# Sensor_Board.net
KiCad netlist of a schematic drawn in EAGLE
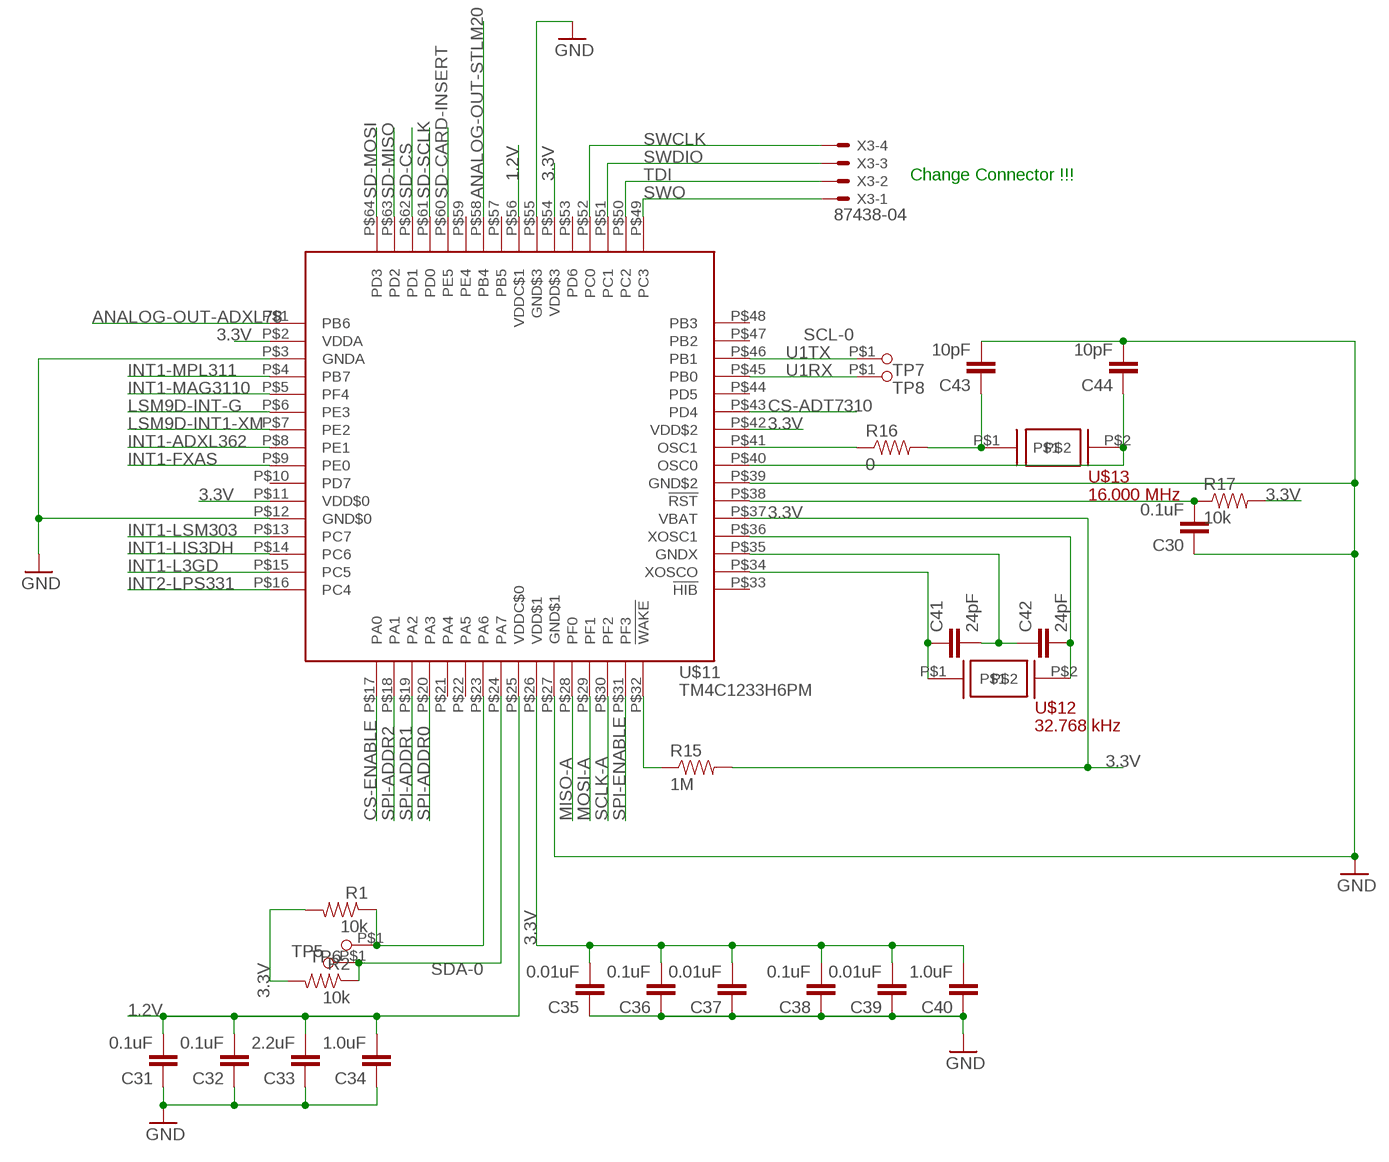
[diagram p0: schematic, sheet 1]
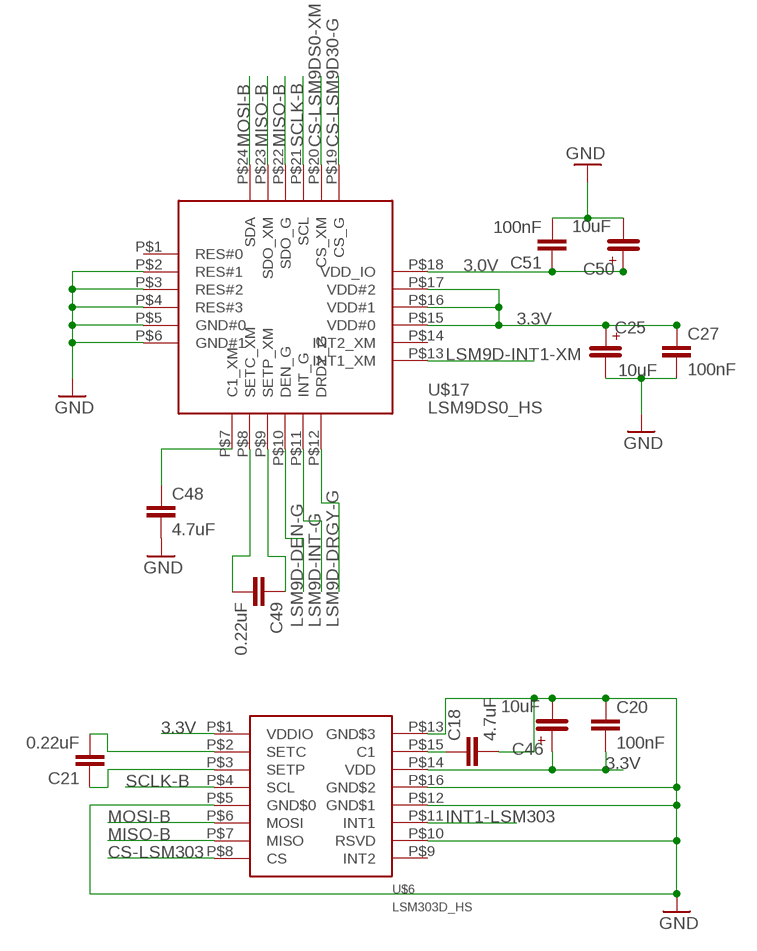
[diagram p1: schematic, sheet 2]
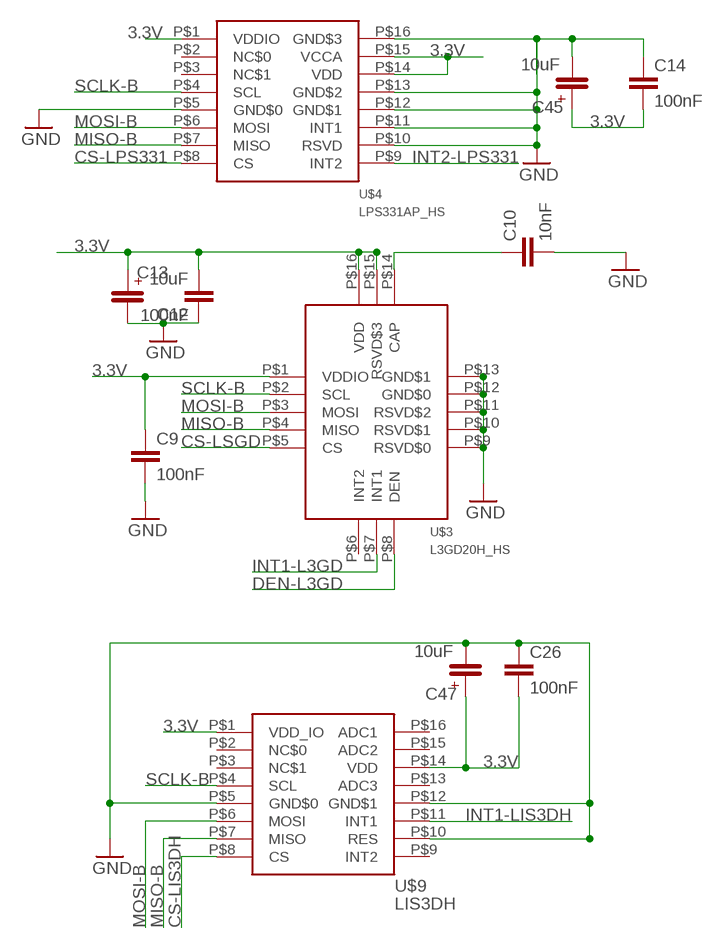
[diagram p2: schematic, sheet 3]
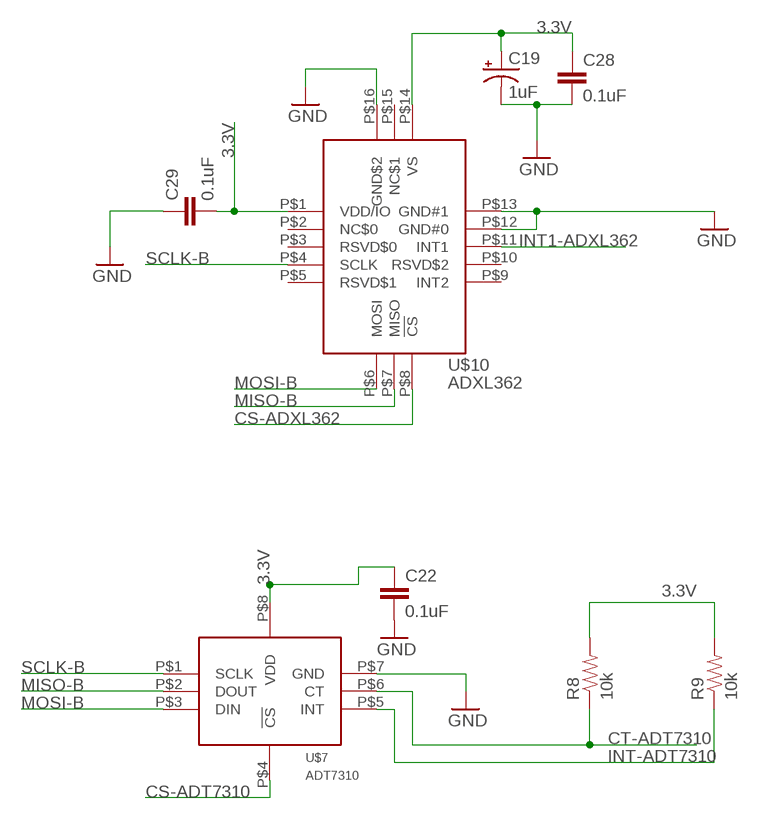
[diagram p3: schematic, sheet 4]
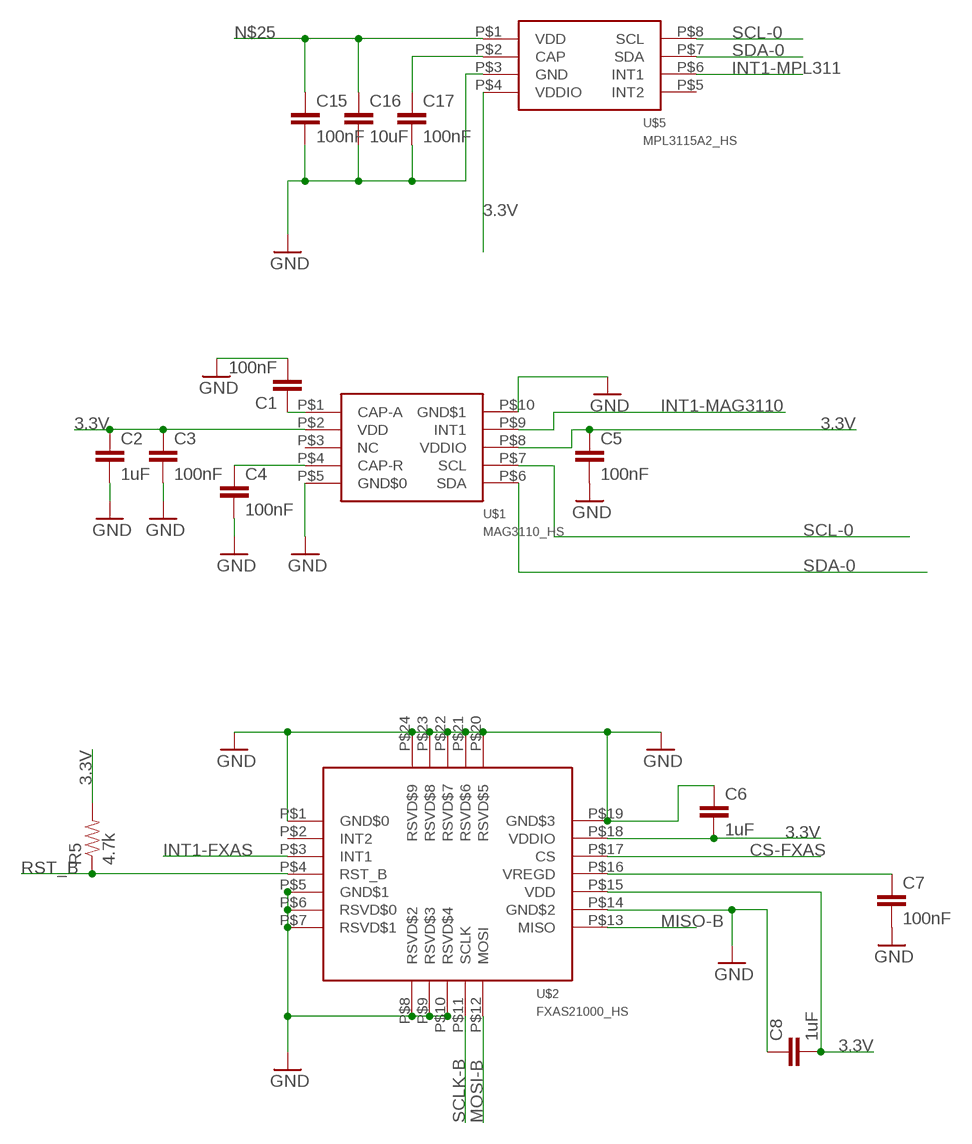
[diagram p4: schematic, sheet 5]
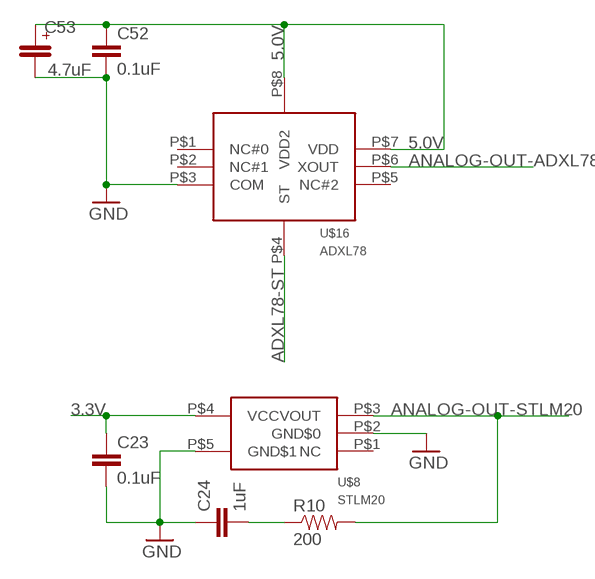
[diagram p5: schematic, sheet 6]
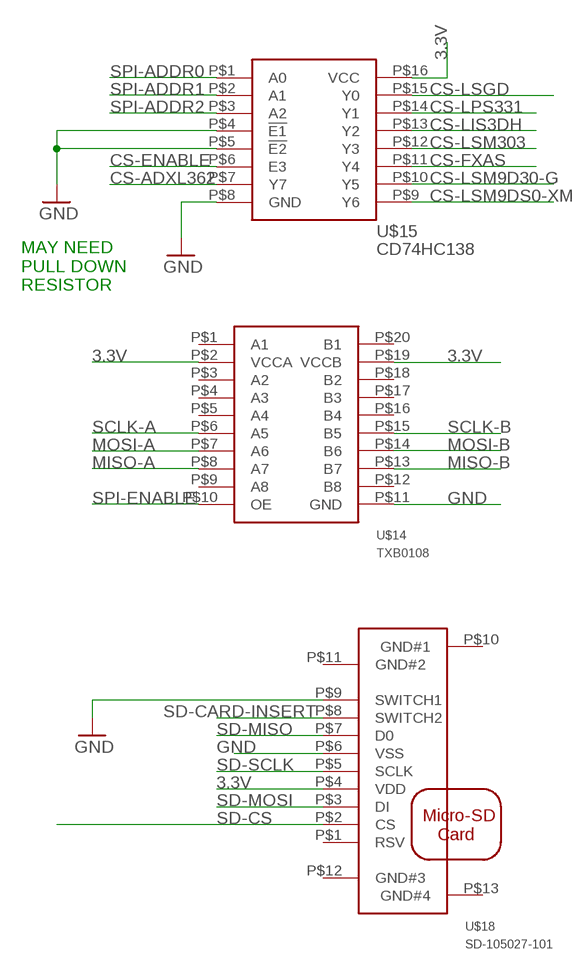
[diagram p6: schematic, sheet 7]
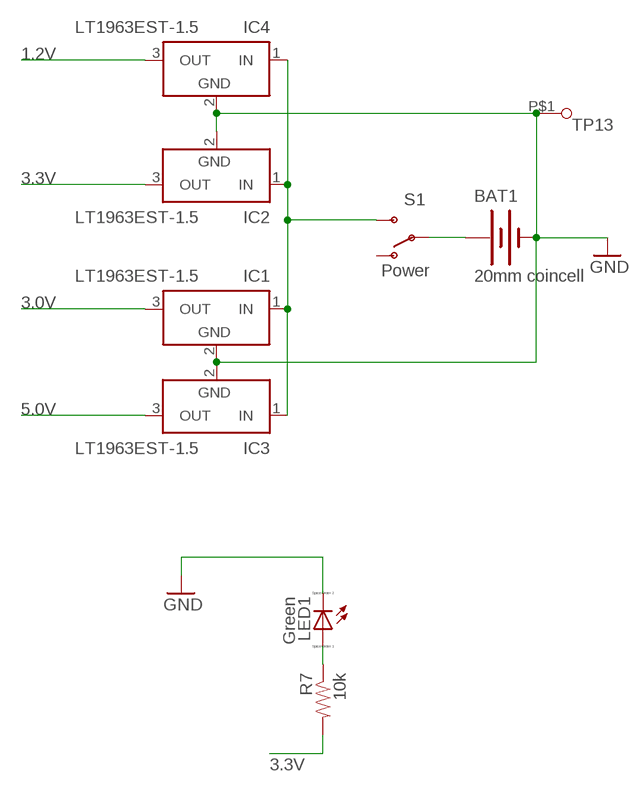
[diagram p7: schematic, sheet 8]

(export (version "E")
  (design (tool "Eeschema 10.0.6"))
  (components
    (comp (ref "C18")
      (value "4.7uF")
      (footprint "eagle-import:0402-CAP")
      (libsource (lib "eagle-import") (part "CAPACITOR"))
    )
    (comp (ref "C20")
      (value "100nF")
      (footprint "eagle-import:0402-CAP")
      (libsource (lib "eagle-import") (part "CAPACITOR"))
    )
    (comp (ref "C21")
      (value "0.22uF")
      (footprint "eagle-import:0402-CAP")
      (libsource (lib "eagle-import") (part "CAPACITOR"))
    )
    (comp (ref "C25")
      (value "10uF")
      (footprint "eagle-import:4.3X7.3SMD")
      (libsource (lib "eagle-import") (part "EEFCD0J100ER"))
    )
    (comp (ref "C27")
      (value "100nF")
      (footprint "eagle-import:0402-CAP")
      (libsource (lib "eagle-import") (part "CAPACITOR"))
    )
    (comp (ref "C46")
      (value "10uF")
      (footprint "eagle-import:4.3X7.3SMD")
      (libsource (lib "eagle-import") (part "EEFCD0J100ER"))
    )
    (comp (ref "C48")
      (value "4.7uF")
      (footprint "eagle-import:0402-CAP")
      (libsource (lib "eagle-import") (part "CAPACITOR"))
    )
    (comp (ref "C49")
      (value "0.22uF")
      (footprint "eagle-import:0402-CAP")
      (libsource (lib "eagle-import") (part "CAPACITOR"))
    )
    (comp (ref "C50")
      (value "10uF")
      (footprint "eagle-import:4.3X7.3SMD")
      (libsource (lib "eagle-import") (part "EEFCD0J100ER"))
    )
    (comp (ref "C51")
      (value "100nF")
      (footprint "eagle-import:0402-CAP")
      (libsource (lib "eagle-import") (part "CAPACITOR"))
    )
    (comp (ref "U$6")
      (value "LSM303D_HS")
      (footprint "eagle-import:LGA-16(3X3)_HS")
      (libsource (lib "eagle-import") (part "LSM303D_HS"))
    )
    (comp (ref "U$17")
      (value "LSM9DS0_HS")
      (footprint "eagle-import:LGA-24(4X4)_HS")
      (libsource (lib "eagle-import") (part "LSM9DS0_HS"))
    )
    (comp (ref "C9")
      (value "100nF")
      (footprint "eagle-import:0402-CAP")
      (libsource (lib "eagle-import") (part "CAPACITOR"))
    )
    (comp (ref "C10")
      (value "10nF")
      (footprint "eagle-import:0402-CAP")
      (libsource (lib "eagle-import") (part "CAPACITOR"))
    )
    (comp (ref "C12")
      (value "10uF")
      (footprint "eagle-import:0402-CAP")
      (libsource (lib "eagle-import") (part "CAPACITOR"))
    )
    (comp (ref "C13")
      (value "100nF")
      (footprint "eagle-import:4.3X7.3SMD")
      (libsource (lib "eagle-import") (part "EEFCD0J100ER"))
    )
    (comp (ref "C14")
      (value "100nF")
      (footprint "eagle-import:0402-CAP")
      (libsource (lib "eagle-import") (part "CAPACITOR"))
    )
    (comp (ref "C26")
      (value "100nF")
      (footprint "eagle-import:0402-CAP")
      (libsource (lib "eagle-import") (part "CAPACITOR"))
    )
    (comp (ref "C45")
      (value "10uF")
      (footprint "eagle-import:4.3X7.3SMD")
      (libsource (lib "eagle-import") (part "EEFCD0J100ER"))
    )
    (comp (ref "C47")
      (value "10uF")
      (footprint "eagle-import:4.3X7.3SMD")
      (libsource (lib "eagle-import") (part "EEFCD0J100ER"))
    )
    (comp (ref "U$3")
      (value "L3GD20H_HS")
      (footprint "eagle-import:LGA-16(3X3)_HS")
      (libsource (lib "eagle-import") (part "L3GD20H_HS"))
    )
    (comp (ref "U$4")
      (value "LPS331AP_HS")
      (footprint "eagle-import:LGA-16(3X3)_HS")
      (libsource (lib "eagle-import") (part "LPS331AP_HS"))
    )
    (comp (ref "U$9")
      (value "LIS3DH")
      (footprint "eagle-import:LGA-16(3X3)_HS")
      (libsource (lib "eagle-import") (part "LIS3DH_HS"))
    )
    (comp (ref "C1")
      (value "100nF")
      (footprint "eagle-import:0402-CAP")
      (libsource (lib "eagle-import") (part "CAPACITOR"))
    )
    (comp (ref "C2")
      (value "1uF")
      (footprint "eagle-import:0402-CAP")
      (libsource (lib "eagle-import") (part "CAPACITOR"))
    )
    (comp (ref "C3")
      (value "100nF")
      (footprint "eagle-import:0402-CAP")
      (libsource (lib "eagle-import") (part "CAPACITOR"))
    )
    (comp (ref "C4")
      (value "100nF")
      (footprint "eagle-import:0402-CAP")
      (libsource (lib "eagle-import") (part "CAPACITOR"))
    )
    (comp (ref "C5")
      (value "100nF")
      (footprint "eagle-import:0402-CAP")
      (libsource (lib "eagle-import") (part "CAPACITOR"))
    )
    (comp (ref "C6")
      (value "1uF")
      (footprint "eagle-import:0402-CAP")
      (libsource (lib "eagle-import") (part "CAPACITOR"))
    )
    (comp (ref "C7")
      (value "100nF")
      (footprint "eagle-import:0402-CAP")
      (libsource (lib "eagle-import") (part "CAPACITOR"))
    )
    (comp (ref "C8")
      (value "1uF")
      (footprint "eagle-import:0402-CAP")
      (libsource (lib "eagle-import") (part "CAPACITOR"))
    )
    (comp (ref "C15")
      (value "100nF")
      (footprint "eagle-import:0402-CAP")
      (libsource (lib "eagle-import") (part "CAPACITOR"))
    )
    (comp (ref "C16")
      (value "10uF")
      (footprint "eagle-import:0402-CAP")
      (libsource (lib "eagle-import") (part "CAPACITOR"))
    )
    (comp (ref "C17")
      (value "100nF")
      (footprint "eagle-import:0402-CAP")
      (libsource (lib "eagle-import") (part "CAPACITOR"))
    )
    (comp (ref "R5")
      (value "4.7k")
      (footprint "eagle-import:0402")
      (libsource (lib "eagle-import") (part "RESISTOR"))
    )
    (comp (ref "U$1")
      (value "MAG3110_HS")
      (footprint "eagle-import:DFN-10(2X2)_HS")
      (libsource (lib "eagle-import") (part "MAG3110_HS"))
    )
    (comp (ref "U$2")
      (value "FXAS21000_HS")
      (footprint "eagle-import:QFN-24(4X4)_HS")
      (libsource (lib "eagle-import") (part "FXAS21000_HS"))
    )
    (comp (ref "U$5")
      (value "MPL3115A2_HS")
      (footprint "eagle-import:LGA-8(5X3)_HS")
      (libsource (lib "eagle-import") (part "MPL3115A2_HS"))
    )
    (comp (ref "U$14")
      (value "TXB0108")
      (footprint "eagle-import:TSSOP-(PW)-20")
      (libsource (lib "eagle-import") (part "TXB0108"))
    )
    (comp (ref "U$15")
      (value "CD74HC138")
      (footprint "eagle-import:SOIC-16")
      (libsource (lib "eagle-import") (part "CD74HC138"))
    )
    (comp (ref "U$18")
      (value "SD-105027-101")
      (footprint "eagle-import:SD-105027-101")
      (libsource (lib "eagle-import") (part "SD-105027-101"))
    )
    (comp (ref "BAT1")
      (value "20mm coincell")
      (footprint "eagle-import:BATTCON_20MM_4LEGS")
      (libsource (lib "eagle-import") (part "BATTERY20MM_4LEGS"))
    )
    (comp (ref "IC1")
      (value "LT1963EST-1.5")
      (footprint "eagle-import:SOT223")
      (libsource (lib "eagle-import") (part "LT1963EST-1.5"))
    )
    (comp (ref "IC2")
      (value "LT1963EST-1.5")
      (footprint "eagle-import:SOT223")
      (libsource (lib "eagle-import") (part "LT1963EST-1.5"))
    )
    (comp (ref "IC3")
      (value "LT1963EST-1.5")
      (footprint "eagle-import:SOT223")
      (libsource (lib "eagle-import") (part "LT1963EST-1.5"))
    )
    (comp (ref "IC4")
      (value "LT1963EST-1.5")
      (footprint "eagle-import:SOT223")
      (libsource (lib "eagle-import") (part "LT1963EST-1.5"))
    )
    (comp (ref "LED1")
      (value "Green")
      (footprint "eagle-import:LED_SML0603")
      (libsource (lib "eagle-import") (part "LED_ESML0603"))
    )
    (comp (ref "R7")
      (value "10k")
      (footprint "eagle-import:0402")
      (libsource (lib "eagle-import") (part "RESISTOR"))
    )
    (comp (ref "S1")
      (value "Power")
      (footprint "eagle-import:SWITCH-SPST-SMD-A")
      (libsource (lib "eagle-import") (part "SWITCH-SPDT-SMD-A"))
    )
    (comp (ref "TP13")
      (value "TESTPAD(ROUND)")
      (footprint "eagle-import:TESTPAD(ROUND)")
      (libsource (lib "eagle-import") (part "TESTPAD(ROUND)"))
    )
    (comp (ref "C19")
      (value "1uF")
      (footprint "eagle-import:EIA6032")
      (libsource (lib "eagle-import") (part "CAP_POL6032"))
    )
    (comp (ref "C22")
      (value "0.1uF")
      (footprint "eagle-import:0402-CAP")
      (libsource (lib "eagle-import") (part "CAPACITOR"))
    )
    (comp (ref "C28")
      (value "0.1uF")
      (footprint "eagle-import:0402-CAP")
      (libsource (lib "eagle-import") (part "CAPACITOR"))
    )
    (comp (ref "C29")
      (value "0.1uF")
      (footprint "eagle-import:0402-CAP")
      (libsource (lib "eagle-import") (part "CAPACITOR"))
    )
    (comp (ref "R8")
      (value "10k")
      (footprint "eagle-import:0402")
      (libsource (lib "eagle-import") (part "RESISTOR"))
    )
    (comp (ref "R9")
      (value "10k")
      (footprint "eagle-import:0402")
      (libsource (lib "eagle-import") (part "RESISTOR"))
    )
    (comp (ref "U$7")
      (value "ADT7310")
      (footprint "eagle-import:SOIC-8(5X6.2)")
      (libsource (lib "eagle-import") (part "ADT7310"))
    )
    (comp (ref "U$10")
      (value "ADXL362")
      (footprint "eagle-import:LGA-16(3X3.25)_HS")
      (libsource (lib "eagle-import") (part "ADXL362_HS"))
    )
    (comp (ref "C23")
      (value "0.1uF")
      (footprint "eagle-import:0402-CAP")
      (libsource (lib "eagle-import") (part "CAPACITOR"))
    )
    (comp (ref "C24")
      (value "1uF")
      (footprint "eagle-import:0402-CAP")
      (libsource (lib "eagle-import") (part "CAPACITOR"))
    )
    (comp (ref "C52")
      (value "0.1uF")
      (footprint "eagle-import:0402-CAP")
      (libsource (lib "eagle-import") (part "CAPACITOR"))
    )
    (comp (ref "C53")
      (value "4.7uF")
      (footprint "eagle-import:4.3X7.3SMD")
      (libsource (lib "eagle-import") (part "EEFCD0J100ER"))
    )
    (comp (ref "R10")
      (value "200")
      (footprint "eagle-import:0402")
      (libsource (lib "eagle-import") (part "RESISTOR"))
    )
    (comp (ref "U$8")
      (value "STLM20")
      (footprint "eagle-import:SOT323-5L")
      (libsource (lib "eagle-import") (part "STLM20"))
    )
    (comp (ref "U$16")
      (value "ADXL78")
      (footprint "eagle-import:LCC-8(5X5)_HS")
      (libsource (lib "eagle-import") (part "ADXL78"))
    )
    (comp (ref "C30")
      (value "0.1uF")
      (footprint "eagle-import:0402-CAP")
      (libsource (lib "eagle-import") (part "CAPACITOR"))
    )
    (comp (ref "C31")
      (value "0.1uF")
      (footprint "eagle-import:0402-CAP")
      (libsource (lib "eagle-import") (part "CAPACITOR"))
    )
    (comp (ref "C32")
      (value "0.1uF")
      (footprint "eagle-import:0402-CAP")
      (libsource (lib "eagle-import") (part "CAPACITOR"))
    )
    (comp (ref "C33")
      (value "2.2uF")
      (footprint "eagle-import:0402-CAP")
      (libsource (lib "eagle-import") (part "CAPACITOR"))
    )
    (comp (ref "C34")
      (value "1.0uF")
      (footprint "eagle-import:0402-CAP")
      (libsource (lib "eagle-import") (part "CAPACITOR"))
    )
    (comp (ref "C35")
      (value "0.01uF")
      (footprint "eagle-import:0402-CAP")
      (libsource (lib "eagle-import") (part "CAPACITOR"))
    )
    (comp (ref "C36")
      (value "0.1uF")
      (footprint "eagle-import:0402-CAP")
      (libsource (lib "eagle-import") (part "CAPACITOR"))
    )
    (comp (ref "C37")
      (value "0.01uF")
      (footprint "eagle-import:0402-CAP")
      (libsource (lib "eagle-import") (part "CAPACITOR"))
    )
    (comp (ref "C38")
      (value "0.1uF")
      (footprint "eagle-import:0402-CAP")
      (libsource (lib "eagle-import") (part "CAPACITOR"))
    )
    (comp (ref "C39")
      (value "0.01uF")
      (footprint "eagle-import:0402-CAP")
      (libsource (lib "eagle-import") (part "CAPACITOR"))
    )
    (comp (ref "C40")
      (value "1.0uF")
      (footprint "eagle-import:0402-CAP")
      (libsource (lib "eagle-import") (part "CAPACITOR"))
    )
    (comp (ref "C41")
      (value "24pF")
      (footprint "eagle-import:0402-CAP")
      (libsource (lib "eagle-import") (part "CAPACITOR"))
    )
    (comp (ref "C42")
      (value "24pF")
      (footprint "eagle-import:0402-CAP")
      (libsource (lib "eagle-import") (part "CAPACITOR"))
    )
    (comp (ref "C43")
      (value "10pF")
      (footprint "eagle-import:0402-CAP")
      (libsource (lib "eagle-import") (part "CAPACITOR"))
    )
    (comp (ref "C44")
      (value "10pF")
      (footprint "eagle-import:0402-CAP")
      (libsource (lib "eagle-import") (part "CAPACITOR"))
    )
    (comp (ref "R1")
      (value "10k")
      (footprint "eagle-import:0402")
      (libsource (lib "eagle-import") (part "RESISTOR"))
    )
    (comp (ref "R2")
      (value "10k")
      (footprint "eagle-import:0402")
      (libsource (lib "eagle-import") (part "RESISTOR"))
    )
    (comp (ref "R15")
      (value "1M")
      (footprint "eagle-import:0402")
      (libsource (lib "eagle-import") (part "RESISTOR"))
    )
    (comp (ref "R16")
      (value "0")
      (footprint "eagle-import:0402")
      (libsource (lib "eagle-import") (part "RESISTOR"))
    )
    (comp (ref "R17")
      (value "10k")
      (footprint "eagle-import:0402")
      (libsource (lib "eagle-import") (part "RESISTOR"))
    )
    (comp (ref "TP5")
      (value "TESTPAD(ROUND)")
      (footprint "eagle-import:TESTPAD(ROUND)")
      (libsource (lib "eagle-import") (part "TESTPAD(ROUND)"))
    )
    (comp (ref "TP6")
      (value "TESTPAD(ROUND)")
      (footprint "eagle-import:TESTPAD(ROUND)")
      (libsource (lib "eagle-import") (part "TESTPAD(ROUND)"))
    )
    (comp (ref "TP7")
      (value "TESTPAD(ROUND)")
      (footprint "eagle-import:TESTPAD(ROUND)")
      (libsource (lib "eagle-import") (part "TESTPAD(ROUND)"))
    )
    (comp (ref "TP8")
      (value "TESTPAD(ROUND)")
      (footprint "eagle-import:TESTPAD(ROUND)")
      (libsource (lib "eagle-import") (part "TESTPAD(ROUND)"))
    )
    (comp (ref "U$11")
      (value "TM4C1233H6PM")
      (footprint "eagle-import:S-PQFP-G64")
      (libsource (lib "eagle-import") (part "TM4C1233H6PM"))
    )
    (comp (ref "U$12")
      (value "32.768 kHz")
      (footprint "eagle-import:CYLINDRICAL-(1.9DIAX6L)")
      (libsource (lib "eagle-import") (part "AB26TRB"))
    )
    (comp (ref "U$13")
      (value "16.000 MHz")
      (footprint "eagle-import:2-SMD")
      (libsource (lib "eagle-import") (part "NX5032GA"))
    )
    (comp (ref "X3")
      (value "87438-04")
      (footprint "eagle-import:87438-04")
      (libsource (lib "eagle-import") (part "87438-04"))
    )
  )
  (nets
    (net (code "1") (name "1.2V") (class "Default")
      (node (ref "C31") (pin "2") (pinfunction "2_2") (pintype "passive"))
      (node (ref "C32") (pin "2") (pinfunction "2_2") (pintype "passive"))
      (node (ref "C33") (pin "2") (pinfunction "2_2") (pintype "passive"))
      (node (ref "C34") (pin "2") (pinfunction "2_2") (pintype "passive"))
      (node (ref "IC4") (pin "3") (pinfunction "OUT_3") (pintype "output"))
      (node (ref "U$11") (pin "P$25") (pinfunction "VDDC$0_P$25") (pintype "bidirectional"))
      (node (ref "U$11") (pin "P$56") (pinfunction "VDDC$1_P$56") (pintype "bidirectional"))
    )
    (net (code "2") (name "3.0V") (class "Default")
      (node (ref "C50") (pin "P$1") (pintype "bidirectional"))
      (node (ref "C51") (pin "1") (pinfunction "1_1") (pintype "passive"))
      (node (ref "IC1") (pin "3") (pinfunction "OUT_3") (pintype "output"))
      (node (ref "U$17") (pin "P$18") (pinfunction "VDD_IO_P$18") (pintype "bidirectional"))
    )
    (net (code "3") (name "3.3V") (class "Default")
      (node (ref "C12") (pin "2") (pinfunction "2_2") (pintype "passive"))
      (node (ref "C13") (pin "P$1") (pintype "bidirectional"))
      (node (ref "C14") (pin "2") (pinfunction "2_2") (pintype "passive"))
      (node (ref "C19") (pin "P$1") (pinfunction "+_P$1") (pintype "passive"))
      (node (ref "C2") (pin "1") (pinfunction "1_1") (pintype "passive"))
      (node (ref "C20") (pin "2") (pinfunction "2_2") (pintype "passive"))
      (node (ref "C22") (pin "1") (pinfunction "1_1") (pintype "passive"))
      (node (ref "C23") (pin "1") (pinfunction "1_1") (pintype "passive"))
      (node (ref "C25") (pin "P$1") (pintype "bidirectional"))
      (node (ref "C26") (pin "2") (pinfunction "2_2") (pintype "passive"))
      (node (ref "C27") (pin "1") (pinfunction "1_1") (pintype "passive"))
      (node (ref "C28") (pin "1") (pinfunction "1_1") (pintype "passive"))
      (node (ref "C29") (pin "2") (pinfunction "2_2") (pintype "passive"))
      (node (ref "C3") (pin "1") (pinfunction "1_1") (pintype "passive"))
      (node (ref "C35") (pin "2") (pinfunction "2_2") (pintype "passive"))
      (node (ref "C36") (pin "2") (pinfunction "2_2") (pintype "passive"))
      (node (ref "C37") (pin "2") (pinfunction "2_2") (pintype "passive"))
      (node (ref "C38") (pin "2") (pinfunction "2_2") (pintype "passive"))
      (node (ref "C39") (pin "2") (pinfunction "2_2") (pintype "passive"))
      (node (ref "C40") (pin "2") (pinfunction "2_2") (pintype "passive"))
      (node (ref "C45") (pin "P$1") (pintype "bidirectional"))
      (node (ref "C46") (pin "P$1") (pintype "bidirectional"))
      (node (ref "C47") (pin "P$1") (pintype "bidirectional"))
      (node (ref "C5") (pin "1") (pinfunction "1_1") (pintype "passive"))
      (node (ref "C6") (pin "2") (pinfunction "2_2") (pintype "passive"))
      (node (ref "C8") (pin "2") (pinfunction "2_2") (pintype "passive"))
      (node (ref "C9") (pin "1") (pinfunction "1_1") (pintype "passive"))
      (node (ref "IC2") (pin "3") (pinfunction "OUT_3") (pintype "output"))
      (node (ref "R1") (pin "2") (pinfunction "2_2") (pintype "passive"))
      (node (ref "R15") (pin "2") (pinfunction "2_2") (pintype "passive"))
      (node (ref "R17") (pin "2") (pinfunction "2_2") (pintype "passive"))
      (node (ref "R2") (pin "2") (pinfunction "2_2") (pintype "passive"))
      (node (ref "R5") (pin "2") (pinfunction "2_2") (pintype "passive"))
      (node (ref "R7") (pin "2") (pinfunction "2_2") (pintype "passive"))
      (node (ref "R8") (pin "2") (pinfunction "2_2") (pintype "passive"))
      (node (ref "R9") (pin "2") (pinfunction "2_2") (pintype "passive"))
      (node (ref "U$1") (pin "P$2") (pinfunction "VDD_P$2") (pintype "bidirectional"))
      (node (ref "U$1") (pin "P$8") (pinfunction "VDDIO_P$8") (pintype "bidirectional"))
      (node (ref "U$10") (pin "P$1") (pinfunction "VDD/IO_P$1") (pintype "bidirectional"))
      (node (ref "U$10") (pin "P$14") (pinfunction "VS_P$14") (pintype "bidirectional"))
      (node (ref "U$11") (pin "P$11") (pinfunction "VDD$0_P$11") (pintype "bidirectional"))
      (node (ref "U$11") (pin "P$2") (pinfunction "VDDA_P$2") (pintype "bidirectional"))
      (node (ref "U$11") (pin "P$26") (pinfunction "VDD$1_P$26") (pintype "bidirectional"))
      (node (ref "U$11") (pin "P$37") (pinfunction "VBAT_P$37") (pintype "bidirectional"))
      (node (ref "U$11") (pin "P$42") (pinfunction "VDD$2_P$42") (pintype "bidirectional"))
      (node (ref "U$11") (pin "P$54") (pinfunction "VDD$3_P$54") (pintype "bidirectional"))
      (node (ref "U$14") (pin "P$19") (pinfunction "VCCB_P$19") (pintype "bidirectional"))
      (node (ref "U$14") (pin "P$2") (pinfunction "VCCA_P$2") (pintype "bidirectional"))
      (node (ref "U$15") (pin "P$16") (pinfunction "VCC_P$16") (pintype "bidirectional"))
      (node (ref "U$17") (pin "P$15") (pinfunction "VDD#0_P$15") (pintype "bidirectional"))
      (node (ref "U$17") (pin "P$16") (pinfunction "VDD#1_P$16") (pintype "bidirectional"))
      (node (ref "U$17") (pin "P$17") (pinfunction "VDD#2_P$17") (pintype "bidirectional"))
      (node (ref "U$18") (pin "P$4") (pinfunction "VDD_P$4") (pintype "bidirectional"))
      (node (ref "U$2") (pin "P$15") (pinfunction "VDD_P$15") (pintype "bidirectional"))
      (node (ref "U$2") (pin "P$18") (pinfunction "VDDIO_P$18") (pintype "bidirectional"))
      (node (ref "U$3") (pin "P$1") (pinfunction "VDDIO_P$1") (pintype "bidirectional"))
      (node (ref "U$3") (pin "P$15") (pinfunction "RSVD$3_P$15") (pintype "bidirectional"))
      (node (ref "U$3") (pin "P$16") (pinfunction "VDD_P$16") (pintype "bidirectional"))
      (node (ref "U$4") (pin "P$1") (pinfunction "VDDIO_P$1") (pintype "bidirectional"))
      (node (ref "U$4") (pin "P$14") (pinfunction "VDD_P$14") (pintype "bidirectional"))
      (node (ref "U$4") (pin "P$15") (pinfunction "VCCA_P$15") (pintype "bidirectional"))
      (node (ref "U$5") (pin "P$4") (pinfunction "VDDIO_P$4") (pintype "bidirectional"))
      (node (ref "U$6") (pin "P$1") (pinfunction "VDDIO_P$1") (pintype "bidirectional"))
      (node (ref "U$6") (pin "P$14") (pinfunction "VDD_P$14") (pintype "bidirectional"))
      (node (ref "U$7") (pin "P$8") (pinfunction "VDD_P$8") (pintype "bidirectional"))
      (node (ref "U$8") (pin "P$4") (pinfunction "VCC_P$4") (pintype "bidirectional"))
      (node (ref "U$9") (pin "P$1") (pinfunction "VDD_IO_P$1") (pintype "bidirectional"))
      (node (ref "U$9") (pin "P$14") (pinfunction "VDD_P$14") (pintype "bidirectional"))
    )
    (net (code "4") (name "5.0V") (class "Default")
      (node (ref "C52") (pin "1") (pinfunction "1_1") (pintype "passive"))
      (node (ref "C53") (pin "P$1") (pintype "bidirectional"))
      (node (ref "IC3") (pin "3") (pinfunction "OUT_3") (pintype "output"))
      (node (ref "U$16") (pin "P$7") (pinfunction "VDD_P$7") (pintype "bidirectional"))
      (node (ref "U$16") (pin "P$8") (pinfunction "VDD2_P$8") (pintype "bidirectional"))
    )
    (net (code "5") (name "ADXL78-ST") (class "Default")
      (node (ref "U$16") (pin "P$4") (pinfunction "ST_P$4") (pintype "bidirectional"))
    )
    (net (code "6") (name "ANALOG-OUT-ADXL78") (class "Default")
      (node (ref "U$11") (pin "P$1") (pinfunction "PB6_P$1") (pintype "bidirectional"))
      (node (ref "U$16") (pin "P$6") (pinfunction "XOUT_P$6") (pintype "bidirectional"))
    )
    (net (code "7") (name "ANALOG-OUT-STLM20") (class "Default")
      (node (ref "R10") (pin "2") (pinfunction "2_2") (pintype "passive"))
      (node (ref "U$11") (pin "P$58") (pinfunction "PB4_P$58") (pintype "bidirectional"))
      (node (ref "U$8") (pin "P$3") (pinfunction "VOUT_P$3") (pintype "bidirectional"))
    )
    (net (code "8") (name "CS-ADT7310") (class "Default")
      (node (ref "U$11") (pin "P$43") (pinfunction "PD4_P$43") (pintype "bidirectional"))
      (node (ref "U$7") (pin "P$4") (pinfunction "~{CS}_P$4") (pintype "bidirectional"))
    )
    (net (code "9") (name "CS-ADXL362") (class "Default")
      (node (ref "U$10") (pin "P$8") (pinfunction "~{CS}_P$8") (pintype "bidirectional"))
      (node (ref "U$15") (pin "P$7") (pinfunction "Y7_P$7") (pintype "bidirectional"))
    )
    (net (code "10") (name "CS-ENABLE") (class "Default")
      (node (ref "U$11") (pin "P$17") (pinfunction "PA0_P$17") (pintype "bidirectional"))
      (node (ref "U$15") (pin "P$6") (pinfunction "E3_P$6") (pintype "bidirectional"))
    )
    (net (code "11") (name "CS-FXAS") (class "Default")
      (node (ref "U$15") (pin "P$11") (pinfunction "Y4_P$11") (pintype "bidirectional"))
      (node (ref "U$2") (pin "P$17") (pinfunction "CS_P$17") (pintype "bidirectional"))
    )
    (net (code "12") (name "CS-LIS3DH") (class "Default")
      (node (ref "U$15") (pin "P$13") (pinfunction "Y2_P$13") (pintype "bidirectional"))
      (node (ref "U$9") (pin "P$8") (pinfunction "CS_P$8") (pintype "bidirectional"))
    )
    (net (code "13") (name "CS-LPS331") (class "Default")
      (node (ref "U$15") (pin "P$14") (pinfunction "Y1_P$14") (pintype "bidirectional"))
      (node (ref "U$4") (pin "P$8") (pinfunction "CS_P$8") (pintype "bidirectional"))
    )
    (net (code "14") (name "CS-LSGD") (class "Default")
      (node (ref "U$15") (pin "P$15") (pinfunction "Y0_P$15") (pintype "bidirectional"))
      (node (ref "U$3") (pin "P$5") (pinfunction "CS_P$5") (pintype "bidirectional"))
    )
    (net (code "15") (name "CS-LSM9D30-G") (class "Default")
      (node (ref "U$15") (pin "P$10") (pinfunction "Y5_P$10") (pintype "bidirectional"))
      (node (ref "U$17") (pin "P$19") (pinfunction "CS_G_P$19") (pintype "bidirectional"))
    )
    (net (code "16") (name "CS-LSM9DS0-XM") (class "Default")
      (node (ref "U$15") (pin "P$9") (pinfunction "Y6_P$9") (pintype "bidirectional"))
      (node (ref "U$17") (pin "P$20") (pinfunction "CS_XM_P$20") (pintype "bidirectional"))
    )
    (net (code "17") (name "CS-LSM303") (class "Default")
      (node (ref "U$15") (pin "P$12") (pinfunction "Y3_P$12") (pintype "bidirectional"))
      (node (ref "U$6") (pin "P$8") (pinfunction "CS_P$8") (pintype "bidirectional"))
    )
    (net (code "18") (name "CT-ADT7310") (class "Default")
      (node (ref "R8") (pin "1") (pinfunction "1_1") (pintype "passive"))
      (node (ref "U$7") (pin "P$6") (pinfunction "CT_P$6") (pintype "bidirectional"))
    )
    (net (code "19") (name "DEN-L3GD") (class "Default")
      (node (ref "U$3") (pin "P$8") (pinfunction "DEN_P$8") (pintype "bidirectional"))
    )
    (net (code "20") (name "GND") (class "Default")
      (node (ref "BAT1") (pin "2") (pinfunction "-_2") (pintype "power_in"))
      (node (ref "C1") (pin "2") (pinfunction "2_2") (pintype "passive"))
      (node (ref "C10") (pin "2") (pinfunction "2_2") (pintype "passive"))
      (node (ref "C12") (pin "1") (pinfunction "1_1") (pintype "passive"))
      (node (ref "C13") (pin "P$2") (pintype "bidirectional"))
      (node (ref "C14") (pin "1") (pinfunction "1_1") (pintype "passive"))
      (node (ref "C15") (pin "2") (pinfunction "2_2") (pintype "passive"))
      (node (ref "C16") (pin "2") (pinfunction "2_2") (pintype "passive"))
      (node (ref "C17") (pin "2") (pinfunction "2_2") (pintype "passive"))
      (node (ref "C18") (pin "2") (pinfunction "2_2") (pintype "passive"))
      (node (ref "C19") (pin "P$2") (pinfunction "-_P$2") (pintype "passive"))
      (node (ref "C2") (pin "2") (pinfunction "2_2") (pintype "passive"))
      (node (ref "C20") (pin "1") (pinfunction "1_1") (pintype "passive"))
      (node (ref "C22") (pin "2") (pinfunction "2_2") (pintype "passive"))
      (node (ref "C23") (pin "2") (pinfunction "2_2") (pintype "passive"))
      (node (ref "C24") (pin "1") (pinfunction "1_1") (pintype "passive"))
      (node (ref "C25") (pin "P$2") (pintype "bidirectional"))
      (node (ref "C26") (pin "1") (pinfunction "1_1") (pintype "passive"))
      (node (ref "C27") (pin "2") (pinfunction "2_2") (pintype "passive"))
      (node (ref "C28") (pin "2") (pinfunction "2_2") (pintype "passive"))
      (node (ref "C29") (pin "1") (pinfunction "1_1") (pintype "passive"))
      (node (ref "C3") (pin "2") (pinfunction "2_2") (pintype "passive"))
      (node (ref "C30") (pin "1") (pinfunction "1_1") (pintype "passive"))
      (node (ref "C31") (pin "1") (pinfunction "1_1") (pintype "passive"))
      (node (ref "C32") (pin "1") (pinfunction "1_1") (pintype "passive"))
      (node (ref "C33") (pin "1") (pinfunction "1_1") (pintype "passive"))
      (node (ref "C34") (pin "1") (pinfunction "1_1") (pintype "passive"))
      (node (ref "C35") (pin "1") (pinfunction "1_1") (pintype "passive"))
      (node (ref "C36") (pin "1") (pinfunction "1_1") (pintype "passive"))
      (node (ref "C37") (pin "1") (pinfunction "1_1") (pintype "passive"))
      (node (ref "C38") (pin "1") (pinfunction "1_1") (pintype "passive"))
      (node (ref "C39") (pin "1") (pinfunction "1_1") (pintype "passive"))
      (node (ref "C4") (pin "2") (pinfunction "2_2") (pintype "passive"))
      (node (ref "C40") (pin "1") (pinfunction "1_1") (pintype "passive"))
      (node (ref "C43") (pin "2") (pinfunction "2_2") (pintype "passive"))
      (node (ref "C44") (pin "2") (pinfunction "2_2") (pintype "passive"))
      (node (ref "C45") (pin "P$2") (pintype "bidirectional"))
      (node (ref "C46") (pin "P$2") (pintype "bidirectional"))
      (node (ref "C47") (pin "P$2") (pintype "bidirectional"))
      (node (ref "C48") (pin "2") (pinfunction "2_2") (pintype "passive"))
      (node (ref "C5") (pin "2") (pinfunction "2_2") (pintype "passive"))
      (node (ref "C50") (pin "P$2") (pintype "bidirectional"))
      (node (ref "C51") (pin "2") (pinfunction "2_2") (pintype "passive"))
      (node (ref "C52") (pin "2") (pinfunction "2_2") (pintype "passive"))
      (node (ref "C53") (pin "P$2") (pintype "bidirectional"))
      (node (ref "C6") (pin "1") (pinfunction "1_1") (pintype "passive"))
      (node (ref "C7") (pin "2") (pinfunction "2_2") (pintype "passive"))
      (node (ref "C8") (pin "1") (pinfunction "1_1") (pintype "passive"))
      (node (ref "C9") (pin "2") (pinfunction "2_2") (pintype "passive"))
      (node (ref "IC1") (pin "2") (pinfunction "GND_2") (pintype "power_in"))
      (node (ref "IC2") (pin "2") (pinfunction "GND_2") (pintype "power_in"))
      (node (ref "IC3") (pin "2") (pinfunction "GND_2") (pintype "power_in"))
      (node (ref "IC4") (pin "2") (pinfunction "GND_2") (pintype "power_in"))
      (node (ref "LED1") (pin "C") (pinfunction "C_C") (pintype "passive"))
      (node (ref "TP13") (pin "P$1") (pinfunction "P$1_P$1") (pintype "bidirectional"))
      (node (ref "U$1") (pin "P$10") (pinfunction "GND$1_P$10") (pintype "bidirectional"))
      (node (ref "U$1") (pin "P$5") (pinfunction "GND$0_P$5") (pintype "bidirectional"))
      (node (ref "U$10") (pin "P$12") (pinfunction "GND#0_P$12") (pintype "bidirectional"))
      (node (ref "U$10") (pin "P$13") (pinfunction "GND#1_P$13") (pintype "bidirectional"))
      (node (ref "U$10") (pin "P$16") (pinfunction "GND$2_P$16") (pintype "bidirectional"))
      (node (ref "U$11") (pin "P$12") (pinfunction "GND$0_P$12") (pintype "bidirectional"))
      (node (ref "U$11") (pin "P$27") (pinfunction "GND$1_P$27") (pintype "bidirectional"))
      (node (ref "U$11") (pin "P$3") (pinfunction "GNDA_P$3") (pintype "bidirectional"))
      (node (ref "U$11") (pin "P$39") (pinfunction "GND$2_P$39") (pintype "bidirectional"))
      (node (ref "U$11") (pin "P$55") (pinfunction "GND$3_P$55") (pintype "bidirectional"))
      (node (ref "U$14") (pin "P$11") (pinfunction "GND_P$11") (pintype "bidirectional"))
      (node (ref "U$15") (pin "P$4") (pinfunction "~{E1}_P$4") (pintype "bidirectional"))
      (node (ref "U$15") (pin "P$5") (pinfunction "~{E2}_P$5") (pintype "bidirectional"))
      (node (ref "U$15") (pin "P$8") (pinfunction "GND_P$8") (pintype "bidirectional"))
      (node (ref "U$16") (pin "P$3") (pinfunction "COM_P$3") (pintype "bidirectional"))
      (node (ref "U$17") (pin "P$2") (pinfunction "RES#1_P$2") (pintype "bidirectional"))
      (node (ref "U$17") (pin "P$3") (pinfunction "RES#2_P$3") (pintype "bidirectional"))
      (node (ref "U$17") (pin "P$4") (pinfunction "RES#3_P$4") (pintype "bidirectional"))
      (node (ref "U$17") (pin "P$5") (pinfunction "GND#0_P$5") (pintype "bidirectional"))
      (node (ref "U$17") (pin "P$6") (pinfunction "GND#1_P$6") (pintype "bidirectional"))
      (node (ref "U$18") (pin "P$6") (pinfunction "VSS_P$6") (pintype "bidirectional"))
      (node (ref "U$18") (pin "P$9") (pinfunction "SWITCH1_P$9") (pintype "bidirectional"))
      (node (ref "U$2") (pin "P$1") (pinfunction "GND$0_P$1") (pintype "bidirectional"))
      (node (ref "U$2") (pin "P$10") (pinfunction "RSVD$4_P$10") (pintype "bidirectional"))
      (node (ref "U$2") (pin "P$14") (pinfunction "GND$2_P$14") (pintype "bidirectional"))
      (node (ref "U$2") (pin "P$19") (pinfunction "GND$3_P$19") (pintype "bidirectional"))
      (node (ref "U$2") (pin "P$20") (pinfunction "RSVD$5_P$20") (pintype "bidirectional"))
      (node (ref "U$2") (pin "P$21") (pinfunction "RSVD$6_P$21") (pintype "bidirectional"))
      (node (ref "U$2") (pin "P$22") (pinfunction "RSVD$7_P$22") (pintype "bidirectional"))
      (node (ref "U$2") (pin "P$23") (pinfunction "RSVD$8_P$23") (pintype "bidirectional"))
      (node (ref "U$2") (pin "P$24") (pinfunction "RSVD$9_P$24") (pintype "bidirectional"))
      (node (ref "U$2") (pin "P$5") (pinfunction "GND$1_P$5") (pintype "bidirectional"))
      (node (ref "U$2") (pin "P$6") (pinfunction "RSVD$0_P$6") (pintype "bidirectional"))
      (node (ref "U$2") (pin "P$7") (pinfunction "RSVD$1_P$7") (pintype "bidirectional"))
      (node (ref "U$2") (pin "P$8") (pinfunction "RSVD$2_P$8") (pintype "bidirectional"))
      (node (ref "U$2") (pin "P$9") (pinfunction "RSVD$3_P$9") (pintype "bidirectional"))
      (node (ref "U$3") (pin "P$10") (pinfunction "RSVD$1_P$10") (pintype "bidirectional"))
      (node (ref "U$3") (pin "P$11") (pinfunction "RSVD$2_P$11") (pintype "bidirectional"))
      (node (ref "U$3") (pin "P$12") (pinfunction "GND$0_P$12") (pintype "bidirectional"))
      (node (ref "U$3") (pin "P$13") (pinfunction "GND$1_P$13") (pintype "bidirectional"))
      (node (ref "U$3") (pin "P$9") (pinfunction "RSVD$0_P$9") (pintype "bidirectional"))
      (node (ref "U$4") (pin "P$10") (pinfunction "RSVD_P$10") (pintype "bidirectional"))
      (node (ref "U$4") (pin "P$11") (pinfunction "INT1_P$11") (pintype "bidirectional"))
      (node (ref "U$4") (pin "P$12") (pinfunction "GND$1_P$12") (pintype "bidirectional"))
      (node (ref "U$4") (pin "P$13") (pinfunction "GND$2_P$13") (pintype "bidirectional"))
      (node (ref "U$4") (pin "P$16") (pinfunction "GND$3_P$16") (pintype "bidirectional"))
      (node (ref "U$4") (pin "P$5") (pinfunction "GND$0_P$5") (pintype "bidirectional"))
      (node (ref "U$5") (pin "P$3") (pinfunction "GND_P$3") (pintype "bidirectional"))
      (node (ref "U$6") (pin "P$10") (pinfunction "RSVD_P$10") (pintype "bidirectional"))
      (node (ref "U$6") (pin "P$12") (pinfunction "GND$1_P$12") (pintype "bidirectional"))
      (node (ref "U$6") (pin "P$13") (pinfunction "GND$3_P$13") (pintype "bidirectional"))
      (node (ref "U$6") (pin "P$16") (pinfunction "GND$2_P$16") (pintype "bidirectional"))
      (node (ref "U$6") (pin "P$5") (pinfunction "GND$0_P$5") (pintype "bidirectional"))
      (node (ref "U$7") (pin "P$7") (pinfunction "GND_P$7") (pintype "bidirectional"))
      (node (ref "U$8") (pin "P$2") (pinfunction "GND$0_P$2") (pintype "bidirectional"))
      (node (ref "U$8") (pin "P$5") (pinfunction "GND$1_P$5") (pintype "bidirectional"))
      (node (ref "U$9") (pin "P$10") (pinfunction "RES_P$10") (pintype "bidirectional"))
      (node (ref "U$9") (pin "P$12") (pinfunction "GND$1_P$12") (pintype "bidirectional"))
      (node (ref "U$9") (pin "P$5") (pinfunction "GND$0_P$5") (pintype "bidirectional"))
    )
    (net (code "21") (name "INT-ADT7310") (class "Default")
      (node (ref "R9") (pin "1") (pinfunction "1_1") (pintype "passive"))
      (node (ref "U$7") (pin "P$5") (pinfunction "INT_P$5") (pintype "bidirectional"))
    )
    (net (code "22") (name "INT1-ADXL362") (class "Default")
      (node (ref "U$10") (pin "P$11") (pinfunction "INT1_P$11") (pintype "bidirectional"))
      (node (ref "U$11") (pin "P$8") (pinfunction "PE1_P$8") (pintype "bidirectional"))
    )
    (net (code "23") (name "INT1-FXAS") (class "Default")
      (node (ref "U$11") (pin "P$9") (pinfunction "PE0_P$9") (pintype "bidirectional"))
      (node (ref "U$2") (pin "P$3") (pinfunction "INT1_P$3") (pintype "bidirectional"))
    )
    (net (code "24") (name "INT1-L3GD") (class "Default")
      (node (ref "U$11") (pin "P$15") (pinfunction "PC5_P$15") (pintype "bidirectional"))
      (node (ref "U$3") (pin "P$7") (pinfunction "INT1_P$7") (pintype "bidirectional"))
    )
    (net (code "25") (name "INT1-LIS3DH") (class "Default")
      (node (ref "U$11") (pin "P$14") (pinfunction "PC6_P$14") (pintype "bidirectional"))
      (node (ref "U$9") (pin "P$11") (pinfunction "INT1_P$11") (pintype "bidirectional"))
    )
    (net (code "26") (name "INT1-LSM303") (class "Default")
      (node (ref "U$11") (pin "P$13") (pinfunction "PC7_P$13") (pintype "bidirectional"))
      (node (ref "U$6") (pin "P$11") (pinfunction "INT1_P$11") (pintype "bidirectional"))
    )
    (net (code "27") (name "INT1-MAG3110") (class "Default")
      (node (ref "U$1") (pin "P$9") (pinfunction "INT1_P$9") (pintype "bidirectional"))
      (node (ref "U$11") (pin "P$5") (pinfunction "PF4_P$5") (pintype "bidirectional"))
    )
    (net (code "28") (name "INT1-MPL311") (class "Default")
      (node (ref "U$11") (pin "P$4") (pinfunction "PB7_P$4") (pintype "bidirectional"))
      (node (ref "U$5") (pin "P$6") (pinfunction "INT1_P$6") (pintype "bidirectional"))
    )
    (net (code "29") (name "INT2-LPS331") (class "Default")
      (node (ref "U$11") (pin "P$16") (pinfunction "PC4_P$16") (pintype "bidirectional"))
      (node (ref "U$4") (pin "P$9") (pinfunction "INT2_P$9") (pintype "bidirectional"))
    )
    (net (code "30") (name "LSM9D-DEN-G") (class "Default")
      (node (ref "U$17") (pin "P$10") (pinfunction "DEN_G_P$10") (pintype "bidirectional"))
    )
    (net (code "31") (name "LSM9D-DRGY-G") (class "Default")
      (node (ref "U$17") (pin "P$12") (pinfunction "DRDY_G_P$12") (pintype "bidirectional"))
    )
    (net (code "32") (name "LSM9D-INT-G") (class "Default")
      (node (ref "U$11") (pin "P$6") (pinfunction "PE3_P$6") (pintype "bidirectional"))
      (node (ref "U$17") (pin "P$11") (pinfunction "INT_G_P$11") (pintype "bidirectional"))
    )
    (net (code "33") (name "LSM9D-INT1-XM") (class "Default")
      (node (ref "U$11") (pin "P$7") (pinfunction "PE2_P$7") (pintype "bidirectional"))
      (node (ref "U$17") (pin "P$13") (pinfunction "INT1_XM_P$13") (pintype "bidirectional"))
    )
    (net (code "34") (name "MISO-A") (class "Default")
      (node (ref "U$11") (pin "P$28") (pinfunction "PF0_P$28") (pintype "bidirectional"))
      (node (ref "U$14") (pin "P$8") (pinfunction "A7_P$8") (pintype "bidirectional"))
    )
    (net (code "35") (name "MISO-B") (class "Default")
      (node (ref "U$10") (pin "P$7") (pinfunction "MISO_P$7") (pintype "bidirectional"))
      (node (ref "U$14") (pin "P$13") (pinfunction "B7_P$13") (pintype "bidirectional"))
      (node (ref "U$17") (pin "P$22") (pinfunction "SDO_G_P$22") (pintype "bidirectional"))
      (node (ref "U$17") (pin "P$23") (pinfunction "SDO_XM_P$23") (pintype "bidirectional"))
      (node (ref "U$2") (pin "P$13") (pinfunction "MISO_P$13") (pintype "bidirectional"))
      (node (ref "U$3") (pin "P$4") (pinfunction "MISO_P$4") (pintype "bidirectional"))
      (node (ref "U$4") (pin "P$7") (pinfunction "MISO_P$7") (pintype "bidirectional"))
      (node (ref "U$6") (pin "P$7") (pinfunction "MISO_P$7") (pintype "bidirectional"))
      (node (ref "U$7") (pin "P$2") (pinfunction "DOUT_P$2") (pintype "bidirectional"))
      (node (ref "U$9") (pin "P$7") (pinfunction "MISO_P$7") (pintype "bidirectional"))
    )
    (net (code "36") (name "MOSI-A") (class "Default")
      (node (ref "U$11") (pin "P$29") (pinfunction "PF1_P$29") (pintype "bidirectional"))
      (node (ref "U$14") (pin "P$7") (pinfunction "A6_P$7") (pintype "bidirectional"))
    )
    (net (code "37") (name "MOSI-B") (class "Default")
      (node (ref "U$10") (pin "P$6") (pinfunction "MOSI_P$6") (pintype "bidirectional"))
      (node (ref "U$14") (pin "P$14") (pinfunction "B6_P$14") (pintype "bidirectional"))
      (node (ref "U$17") (pin "P$24") (pinfunction "SDA_P$24") (pintype "bidirectional"))
      (node (ref "U$2") (pin "P$12") (pinfunction "MOSI_P$12") (pintype "bidirectional"))
      (node (ref "U$3") (pin "P$3") (pinfunction "MOSI_P$3") (pintype "bidirectional"))
      (node (ref "U$4") (pin "P$6") (pinfunction "MOSI_P$6") (pintype "bidirectional"))
      (node (ref "U$6") (pin "P$6") (pinfunction "MOSI_P$6") (pintype "bidirectional"))
      (node (ref "U$7") (pin "P$3") (pinfunction "DIN_P$3") (pintype "bidirectional"))
      (node (ref "U$9") (pin "P$6") (pinfunction "MOSI_P$6") (pintype "bidirectional"))
    )
    (net (code "38") (name "N$25") (class "Default")
      (node (ref "C15") (pin "1") (pinfunction "1_1") (pintype "passive"))
      (node (ref "C16") (pin "1") (pinfunction "1_1") (pintype "passive"))
      (node (ref "U$5") (pin "P$1") (pinfunction "VDD_P$1") (pintype "bidirectional"))
    )
    (net (code "39") (name "Net-(BAT1-+)") (class "Default")
      (node (ref "BAT1") (pin "1") (pinfunction "+_1") (pintype "power_in"))
      (node (ref "S1") (pin "2") (pinfunction "P_2") (pintype "passive"))
    )
    (net (code "40") (name "Net-(C24-Pad2)") (class "Default")
      (node (ref "C24") (pin "2") (pinfunction "2_2") (pintype "passive"))
      (node (ref "R10") (pin "1") (pinfunction "1_1") (pintype "passive"))
    )
    (net (code "41") (name "Net-(C43-Pad1)") (class "Default")
      (node (ref "C43") (pin "1") (pinfunction "1_1") (pintype "passive"))
      (node (ref "R16") (pin "2") (pinfunction "2_2") (pintype "passive"))
      (node (ref "U$13") (pin "P$1") (pinfunction "P$1_P$1") (pintype "bidirectional"))
    )
    (net (code "42") (name "Net-(IC1A-IN)") (class "Default")
      (node (ref "IC1") (pin "1") (pinfunction "IN_1") (pintype "input"))
      (node (ref "IC2") (pin "1") (pinfunction "IN_1") (pintype "input"))
      (node (ref "IC3") (pin "1") (pinfunction "IN_1") (pintype "input"))
      (node (ref "IC4") (pin "1") (pinfunction "IN_1") (pintype "input"))
      (node (ref "S1") (pin "3") (pinfunction "S_3") (pintype "passive"))
    )
    (net (code "43") (name "Net-(LED1-PadA)") (class "Default")
      (node (ref "LED1") (pin "A") (pinfunction "A_A") (pintype "passive"))
      (node (ref "R7") (pin "1") (pinfunction "1_1") (pintype "passive"))
    )
    (net (code "44") (name "Net-(U$1-CAP-A)") (class "Default")
      (node (ref "C1") (pin "1") (pinfunction "1_1") (pintype "passive"))
      (node (ref "U$1") (pin "P$1") (pinfunction "CAP-A_P$1") (pintype "bidirectional"))
    )
    (net (code "45") (name "Net-(U$1-CAP-R)") (class "Default")
      (node (ref "C4") (pin "1") (pinfunction "1_1") (pintype "passive"))
      (node (ref "U$1") (pin "P$4") (pinfunction "CAP-R_P$4") (pintype "bidirectional"))
    )
    (net (code "46") (name "Net-(U$2-VREGD)") (class "Default")
      (node (ref "C7") (pin "1") (pinfunction "1_1") (pintype "passive"))
      (node (ref "U$2") (pin "P$16") (pinfunction "VREGD_P$16") (pintype "bidirectional"))
    )
    (net (code "47") (name "Net-(U$3-CAP)") (class "Default")
      (node (ref "C10") (pin "1") (pinfunction "1_1") (pintype "passive"))
      (node (ref "U$3") (pin "P$14") (pinfunction "CAP_P$14") (pintype "bidirectional"))
    )
    (net (code "48") (name "Net-(U$5-CAP)") (class "Default")
      (node (ref "C17") (pin "1") (pinfunction "1_1") (pintype "passive"))
      (node (ref "U$5") (pin "P$2") (pinfunction "CAP_P$2") (pintype "bidirectional"))
    )
    (net (code "49") (name "Net-(U$6-C1)") (class "Default")
      (node (ref "C18") (pin "1") (pinfunction "1_1") (pintype "passive"))
      (node (ref "U$6") (pin "P$15") (pinfunction "C1_P$15") (pintype "bidirectional"))
    )
    (net (code "50") (name "Net-(U$6-SETC)") (class "Default")
      (node (ref "C21") (pin "2") (pinfunction "2_2") (pintype "passive"))
      (node (ref "U$6") (pin "P$2") (pinfunction "SETC_P$2") (pintype "bidirectional"))
    )
    (net (code "51") (name "Net-(U$6-SETP)") (class "Default")
      (node (ref "C21") (pin "1") (pinfunction "1_1") (pintype "passive"))
      (node (ref "U$6") (pin "P$3") (pinfunction "SETP_P$3") (pintype "bidirectional"))
    )
    (net (code "52") (name "Net-(U$11-GNDX)") (class "Default")
      (node (ref "C41") (pin "2") (pinfunction "2_2") (pintype "passive"))
      (node (ref "C42") (pin "1") (pinfunction "1_1") (pintype "passive"))
      (node (ref "U$11") (pin "P$35") (pinfunction "GNDX_P$35") (pintype "bidirectional"))
    )
    (net (code "53") (name "Net-(U$11-OSC0)") (class "Default")
      (node (ref "C44") (pin "1") (pinfunction "1_1") (pintype "passive"))
      (node (ref "U$11") (pin "P$40") (pinfunction "OSC0_P$40") (pintype "bidirectional"))
      (node (ref "U$13") (pin "P$2") (pinfunction "P$2_P$2") (pintype "bidirectional"))
    )
    (net (code "54") (name "Net-(U$11-OSC1)") (class "Default")
      (node (ref "R16") (pin "1") (pinfunction "1_1") (pintype "passive"))
      (node (ref "U$11") (pin "P$41") (pinfunction "OSC1_P$41") (pintype "bidirectional"))
    )
    (net (code "55") (name "Net-(U$11-XOSC1)") (class "Default")
      (node (ref "C42") (pin "2") (pinfunction "2_2") (pintype "passive"))
      (node (ref "U$11") (pin "P$36") (pinfunction "XOSC1_P$36") (pintype "bidirectional"))
      (node (ref "U$12") (pin "P$2") (pinfunction "P$2_P$2") (pintype "bidirectional"))
    )
    (net (code "56") (name "Net-(U$11-XOSCO)") (class "Default")
      (node (ref "C41") (pin "1") (pinfunction "1_1") (pintype "passive"))
      (node (ref "U$11") (pin "P$34") (pinfunction "XOSCO_P$34") (pintype "bidirectional"))
      (node (ref "U$12") (pin "P$1") (pinfunction "P$1_P$1") (pintype "bidirectional"))
    )
    (net (code "57") (name "Net-(U$11-~{RST})") (class "Default")
      (node (ref "C30") (pin "2") (pinfunction "2_2") (pintype "passive"))
      (node (ref "R17") (pin "1") (pinfunction "1_1") (pintype "passive"))
      (node (ref "U$11") (pin "P$38") (pinfunction "~{RST}_P$38") (pintype "bidirectional"))
    )
    (net (code "58") (name "Net-(U$11-~{WAKE})") (class "Default")
      (node (ref "R15") (pin "1") (pinfunction "1_1") (pintype "passive"))
      (node (ref "U$11") (pin "P$32") (pinfunction "~{WAKE}_P$32") (pintype "bidirectional"))
    )
    (net (code "59") (name "Net-(U$17-C1_XM)") (class "Default")
      (node (ref "C48") (pin "1") (pinfunction "1_1") (pintype "passive"))
      (node (ref "U$17") (pin "P$7") (pinfunction "C1_XM_P$7") (pintype "bidirectional"))
    )
    (net (code "60") (name "Net-(U$17-SETC_XM)") (class "Default")
      (node (ref "C49") (pin "2") (pinfunction "2_2") (pintype "passive"))
      (node (ref "U$17") (pin "P$8") (pinfunction "SETC_XM_P$8") (pintype "bidirectional"))
    )
    (net (code "61") (name "Net-(U$17-SETP_XM)") (class "Default")
      (node (ref "C49") (pin "1") (pinfunction "1_1") (pintype "passive"))
      (node (ref "U$17") (pin "P$9") (pinfunction "SETP_XM_P$9") (pintype "bidirectional"))
    )
    (net (code "62") (name "RST_B") (class "Default")
      (node (ref "R5") (pin "1") (pinfunction "1_1") (pintype "passive"))
      (node (ref "U$2") (pin "P$4") (pinfunction "RST_B_P$4") (pintype "bidirectional"))
    )
    (net (code "63") (name "SCL-0") (class "Default")
      (node (ref "R1") (pin "1") (pinfunction "1_1") (pintype "passive"))
      (node (ref "TP6") (pin "P$1") (pinfunction "P$1_P$1") (pintype "bidirectional"))
      (node (ref "U$1") (pin "P$7") (pinfunction "SCL_P$7") (pintype "bidirectional"))
      (node (ref "U$11") (pin "P$23") (pinfunction "PA6_P$23") (pintype "bidirectional"))
      (node (ref "U$5") (pin "P$8") (pinfunction "SCL_P$8") (pintype "bidirectional"))
    )
    (net (code "64") (name "SCLK-A") (class "Default")
      (node (ref "U$11") (pin "P$30") (pinfunction "PF2_P$30") (pintype "bidirectional"))
      (node (ref "U$14") (pin "P$6") (pinfunction "A5_P$6") (pintype "bidirectional"))
    )
    (net (code "65") (name "SCLK-B") (class "Default")
      (node (ref "U$10") (pin "P$4") (pinfunction "SCLK_P$4") (pintype "bidirectional"))
      (node (ref "U$14") (pin "P$15") (pinfunction "B5_P$15") (pintype "bidirectional"))
      (node (ref "U$17") (pin "P$21") (pinfunction "SCL_P$21") (pintype "bidirectional"))
      (node (ref "U$2") (pin "P$11") (pinfunction "SCLK_P$11") (pintype "bidirectional"))
      (node (ref "U$3") (pin "P$2") (pinfunction "SCL_P$2") (pintype "bidirectional"))
      (node (ref "U$4") (pin "P$4") (pinfunction "SCL_P$4") (pintype "bidirectional"))
      (node (ref "U$6") (pin "P$4") (pinfunction "SCL_P$4") (pintype "bidirectional"))
      (node (ref "U$7") (pin "P$1") (pinfunction "SCLK_P$1") (pintype "bidirectional"))
      (node (ref "U$9") (pin "P$4") (pinfunction "SCL_P$4") (pintype "bidirectional"))
    )
    (net (code "66") (name "SD-CARD-INSERT") (class "Default")
      (node (ref "U$11") (pin "P$60") (pinfunction "PE5_P$60") (pintype "bidirectional"))
      (node (ref "U$18") (pin "P$8") (pinfunction "SWITCH2_P$8") (pintype "bidirectional"))
    )
    (net (code "67") (name "SD-CS") (class "Default")
      (node (ref "U$11") (pin "P$62") (pinfunction "PD1_P$62") (pintype "bidirectional"))
      (node (ref "U$18") (pin "P$2") (pinfunction "CS_P$2") (pintype "bidirectional"))
    )
    (net (code "68") (name "SD-MISO") (class "Default")
      (node (ref "U$11") (pin "P$63") (pinfunction "PD2_P$63") (pintype "bidirectional"))
      (node (ref "U$18") (pin "P$7") (pinfunction "D0_P$7") (pintype "bidirectional"))
    )
    (net (code "69") (name "SD-MOSI") (class "Default")
      (node (ref "U$11") (pin "P$64") (pinfunction "PD3_P$64") (pintype "bidirectional"))
      (node (ref "U$18") (pin "P$3") (pinfunction "DI_P$3") (pintype "bidirectional"))
    )
    (net (code "70") (name "SD-SCLK") (class "Default")
      (node (ref "U$11") (pin "P$61") (pinfunction "PD0_P$61") (pintype "bidirectional"))
      (node (ref "U$18") (pin "P$5") (pinfunction "SCLK_P$5") (pintype "bidirectional"))
    )
    (net (code "71") (name "SDA-0") (class "Default")
      (node (ref "R2") (pin "1") (pinfunction "1_1") (pintype "passive"))
      (node (ref "TP5") (pin "P$1") (pinfunction "P$1_P$1") (pintype "bidirectional"))
      (node (ref "U$1") (pin "P$6") (pinfunction "SDA_P$6") (pintype "bidirectional"))
      (node (ref "U$11") (pin "P$24") (pinfunction "PA7_P$24") (pintype "bidirectional"))
      (node (ref "U$5") (pin "P$7") (pinfunction "SDA_P$7") (pintype "bidirectional"))
    )
    (net (code "72") (name "SPI-ADDR0") (class "Default")
      (node (ref "U$11") (pin "P$20") (pinfunction "PA3_P$20") (pintype "bidirectional"))
      (node (ref "U$15") (pin "P$1") (pinfunction "A0_P$1") (pintype "bidirectional"))
    )
    (net (code "73") (name "SPI-ADDR1") (class "Default")
      (node (ref "U$11") (pin "P$19") (pinfunction "PA2_P$19") (pintype "bidirectional"))
      (node (ref "U$15") (pin "P$2") (pinfunction "A1_P$2") (pintype "bidirectional"))
    )
    (net (code "74") (name "SPI-ADDR2") (class "Default")
      (node (ref "U$11") (pin "P$18") (pinfunction "PA1_P$18") (pintype "bidirectional"))
      (node (ref "U$15") (pin "P$3") (pinfunction "A2_P$3") (pintype "bidirectional"))
    )
    (net (code "75") (name "SPI-ENABLE") (class "Default")
      (node (ref "U$11") (pin "P$31") (pinfunction "PF3_P$31") (pintype "bidirectional"))
      (node (ref "U$14") (pin "P$10") (pinfunction "OE_P$10") (pintype "bidirectional"))
    )
    (net (code "76") (name "SWCLK") (class "Default")
      (node (ref "U$11") (pin "P$52") (pinfunction "PC0_P$52") (pintype "bidirectional"))
      (node (ref "X3") (pin "4") (pinfunction "S_4") (pintype "passive"))
    )
    (net (code "77") (name "SWDIO") (class "Default")
      (node (ref "U$11") (pin "P$51") (pinfunction "PC1_P$51") (pintype "bidirectional"))
      (node (ref "X3") (pin "3") (pinfunction "S_3") (pintype "passive"))
    )
    (net (code "78") (name "SWO") (class "Default")
      (node (ref "U$11") (pin "P$49") (pinfunction "PC3_P$49") (pintype "bidirectional"))
      (node (ref "X3") (pin "1") (pinfunction "S_1") (pintype "passive"))
    )
    (net (code "79") (name "TDI") (class "Default")
      (node (ref "U$11") (pin "P$50") (pinfunction "PC2_P$50") (pintype "bidirectional"))
      (node (ref "X3") (pin "2") (pinfunction "S_2") (pintype "passive"))
    )
    (net (code "80") (name "U1RX") (class "Default")
      (node (ref "TP8") (pin "P$1") (pinfunction "P$1_P$1") (pintype "bidirectional"))
      (node (ref "U$11") (pin "P$45") (pinfunction "PB0_P$45") (pintype "bidirectional"))
    )
    (net (code "81") (name "U1TX") (class "Default")
      (node (ref "TP7") (pin "P$1") (pinfunction "P$1_P$1") (pintype "bidirectional"))
      (node (ref "U$11") (pin "P$46") (pinfunction "PB1_P$46") (pintype "bidirectional"))
    )
    (net (code "82") (name "unconnected-(S1-O-Pad1)") (class "Default")
      (node (ref "S1") (pin "1") (pinfunction "O_1") (pintype "passive"))
    )
    (net (code "83") (name "unconnected-(U$1-NC-PadP$3)") (class "Default")
      (node (ref "U$1") (pin "P$3") (pinfunction "NC_P$3") (pintype "bidirectional"))
    )
    (net (code "84") (name "unconnected-(U$2-INT2-PadP$2)") (class "Default")
      (node (ref "U$2") (pin "P$2") (pinfunction "INT2_P$2") (pintype "bidirectional"))
    )
    (net (code "85") (name "unconnected-(U$3-INT2-PadP$6)") (class "Default")
      (node (ref "U$3") (pin "P$6") (pinfunction "INT2_P$6") (pintype "bidirectional"))
    )
    (net (code "86") (name "unconnected-(U$4-NC$0-PadP$2)") (class "Default")
      (node (ref "U$4") (pin "P$2") (pinfunction "NC$0_P$2") (pintype "bidirectional"))
    )
    (net (code "87") (name "unconnected-(U$4-NC$1-PadP$3)") (class "Default")
      (node (ref "U$4") (pin "P$3") (pinfunction "NC$1_P$3") (pintype "bidirectional"))
    )
    (net (code "88") (name "unconnected-(U$5-INT2-PadP$5)") (class "Default")
      (node (ref "U$5") (pin "P$5") (pinfunction "INT2_P$5") (pintype "bidirectional"))
    )
    (net (code "89") (name "unconnected-(U$6-INT2-PadP$9)") (class "Default")
      (node (ref "U$6") (pin "P$9") (pinfunction "INT2_P$9") (pintype "bidirectional"))
    )
    (net (code "90") (name "unconnected-(U$8-NC-PadP$1)") (class "Default")
      (node (ref "U$8") (pin "P$1") (pinfunction "NC_P$1") (pintype "bidirectional"))
    )
    (net (code "91") (name "unconnected-(U$9-ADC1-PadP$16)") (class "Default")
      (node (ref "U$9") (pin "P$16") (pinfunction "ADC1_P$16") (pintype "bidirectional"))
    )
    (net (code "92") (name "unconnected-(U$9-ADC2-PadP$15)") (class "Default")
      (node (ref "U$9") (pin "P$15") (pinfunction "ADC2_P$15") (pintype "bidirectional"))
    )
    (net (code "93") (name "unconnected-(U$9-ADC3-PadP$13)") (class "Default")
      (node (ref "U$9") (pin "P$13") (pinfunction "ADC3_P$13") (pintype "bidirectional"))
    )
    (net (code "94") (name "unconnected-(U$9-INT2-PadP$9)") (class "Default")
      (node (ref "U$9") (pin "P$9") (pinfunction "INT2_P$9") (pintype "bidirectional"))
    )
    (net (code "95") (name "unconnected-(U$9-NC$0-PadP$2)") (class "Default")
      (node (ref "U$9") (pin "P$2") (pinfunction "NC$0_P$2") (pintype "bidirectional"))
    )
    (net (code "96") (name "unconnected-(U$9-NC$1-PadP$3)") (class "Default")
      (node (ref "U$9") (pin "P$3") (pinfunction "NC$1_P$3") (pintype "bidirectional"))
    )
    (net (code "97") (name "unconnected-(U$10-INT2-PadP$9)") (class "Default")
      (node (ref "U$10") (pin "P$9") (pinfunction "INT2_P$9") (pintype "bidirectional"))
    )
    (net (code "98") (name "unconnected-(U$10-NC$0-PadP$2)") (class "Default")
      (node (ref "U$10") (pin "P$2") (pinfunction "NC$0_P$2") (pintype "bidirectional"))
    )
    (net (code "99") (name "unconnected-(U$10-NC$1-PadP$15)") (class "Default")
      (node (ref "U$10") (pin "P$15") (pinfunction "NC$1_P$15") (pintype "bidirectional"))
    )
    (net (code "100") (name "unconnected-(U$10-RSVD$0-PadP$3)") (class "Default")
      (node (ref "U$10") (pin "P$3") (pinfunction "RSVD$0_P$3") (pintype "bidirectional"))
    )
    (net (code "101") (name "unconnected-(U$10-RSVD$1-PadP$5)") (class "Default")
      (node (ref "U$10") (pin "P$5") (pinfunction "RSVD$1_P$5") (pintype "bidirectional"))
    )
    (net (code "102") (name "unconnected-(U$10-RSVD$2-PadP$10)") (class "Default")
      (node (ref "U$10") (pin "P$10") (pinfunction "RSVD$2_P$10") (pintype "bidirectional"))
    )
    (net (code "103") (name "unconnected-(U$11-PA4-PadP$21)") (class "Default")
      (node (ref "U$11") (pin "P$21") (pinfunction "PA4_P$21") (pintype "bidirectional"))
    )
    (net (code "104") (name "unconnected-(U$11-PA5-PadP$22)") (class "Default")
      (node (ref "U$11") (pin "P$22") (pinfunction "PA5_P$22") (pintype "bidirectional"))
    )
    (net (code "105") (name "unconnected-(U$11-PB2-PadP$47)") (class "Default")
      (node (ref "U$11") (pin "P$47") (pinfunction "PB2_P$47") (pintype "bidirectional"))
    )
    (net (code "106") (name "unconnected-(U$11-PB3-PadP$48)") (class "Default")
      (node (ref "U$11") (pin "P$48") (pinfunction "PB3_P$48") (pintype "bidirectional"))
    )
    (net (code "107") (name "unconnected-(U$11-PB5-PadP$57)") (class "Default")
      (node (ref "U$11") (pin "P$57") (pinfunction "PB5_P$57") (pintype "bidirectional"))
    )
    (net (code "108") (name "unconnected-(U$11-PD5-PadP$44)") (class "Default")
      (node (ref "U$11") (pin "P$44") (pinfunction "PD5_P$44") (pintype "bidirectional"))
    )
    (net (code "109") (name "unconnected-(U$11-PD6-PadP$53)") (class "Default")
      (node (ref "U$11") (pin "P$53") (pinfunction "PD6_P$53") (pintype "bidirectional"))
    )
    (net (code "110") (name "unconnected-(U$11-PD7-PadP$10)") (class "Default")
      (node (ref "U$11") (pin "P$10") (pinfunction "PD7_P$10") (pintype "bidirectional"))
    )
    (net (code "111") (name "unconnected-(U$11-PE4-PadP$59)") (class "Default")
      (node (ref "U$11") (pin "P$59") (pinfunction "PE4_P$59") (pintype "bidirectional"))
    )
    (net (code "112") (name "unconnected-(U$11-~{HIB}-PadP$33)") (class "Default")
      (node (ref "U$11") (pin "P$33") (pinfunction "~{HIB}_P$33") (pintype "bidirectional"))
    )
    (net (code "113") (name "unconnected-(U$14-A1-PadP$1)") (class "Default")
      (node (ref "U$14") (pin "P$1") (pinfunction "A1_P$1") (pintype "bidirectional"))
    )
    (net (code "114") (name "unconnected-(U$14-A2-PadP$3)") (class "Default")
      (node (ref "U$14") (pin "P$3") (pinfunction "A2_P$3") (pintype "bidirectional"))
    )
    (net (code "115") (name "unconnected-(U$14-A3-PadP$4)") (class "Default")
      (node (ref "U$14") (pin "P$4") (pinfunction "A3_P$4") (pintype "bidirectional"))
    )
    (net (code "116") (name "unconnected-(U$14-A4-PadP$5)") (class "Default")
      (node (ref "U$14") (pin "P$5") (pinfunction "A4_P$5") (pintype "bidirectional"))
    )
    (net (code "117") (name "unconnected-(U$14-A8-PadP$9)") (class "Default")
      (node (ref "U$14") (pin "P$9") (pinfunction "A8_P$9") (pintype "bidirectional"))
    )
    (net (code "118") (name "unconnected-(U$14-B1-PadP$20)") (class "Default")
      (node (ref "U$14") (pin "P$20") (pinfunction "B1_P$20") (pintype "bidirectional"))
    )
    (net (code "119") (name "unconnected-(U$14-B2-PadP$18)") (class "Default")
      (node (ref "U$14") (pin "P$18") (pinfunction "B2_P$18") (pintype "bidirectional"))
    )
    (net (code "120") (name "unconnected-(U$14-B3-PadP$17)") (class "Default")
      (node (ref "U$14") (pin "P$17") (pinfunction "B3_P$17") (pintype "bidirectional"))
    )
    (net (code "121") (name "unconnected-(U$14-B4-PadP$16)") (class "Default")
      (node (ref "U$14") (pin "P$16") (pinfunction "B4_P$16") (pintype "bidirectional"))
    )
    (net (code "122") (name "unconnected-(U$14-B8-PadP$12)") (class "Default")
      (node (ref "U$14") (pin "P$12") (pinfunction "B8_P$12") (pintype "bidirectional"))
    )
    (net (code "123") (name "unconnected-(U$16-NC#0-PadP$1)") (class "Default")
      (node (ref "U$16") (pin "P$1") (pinfunction "NC#0_P$1") (pintype "bidirectional"))
    )
    (net (code "124") (name "unconnected-(U$16-NC#1-PadP$2)") (class "Default")
      (node (ref "U$16") (pin "P$2") (pinfunction "NC#1_P$2") (pintype "bidirectional"))
    )
    (net (code "125") (name "unconnected-(U$16-NC#2-PadP$5)") (class "Default")
      (node (ref "U$16") (pin "P$5") (pinfunction "NC#2_P$5") (pintype "bidirectional"))
    )
    (net (code "126") (name "unconnected-(U$17-INT2_XM-PadP$14)") (class "Default")
      (node (ref "U$17") (pin "P$14") (pinfunction "INT2_XM_P$14") (pintype "bidirectional"))
    )
    (net (code "127") (name "unconnected-(U$17-RES#0-PadP$1)") (class "Default")
      (node (ref "U$17") (pin "P$1") (pinfunction "RES#0_P$1") (pintype "bidirectional"))
    )
    (net (code "128") (name "unconnected-(U$18-GND#1-PadP$10)") (class "Default")
      (node (ref "U$18") (pin "P$10") (pinfunction "GND#1_P$10") (pintype "bidirectional"))
    )
    (net (code "129") (name "unconnected-(U$18-GND#2-PadP$11)") (class "Default")
      (node (ref "U$18") (pin "P$11") (pinfunction "GND#2_P$11") (pintype "bidirectional"))
    )
    (net (code "130") (name "unconnected-(U$18-GND#3-PadP$12)") (class "Default")
      (node (ref "U$18") (pin "P$12") (pinfunction "GND#3_P$12") (pintype "bidirectional"))
    )
    (net (code "131") (name "unconnected-(U$18-GND#4-PadP$13)") (class "Default")
      (node (ref "U$18") (pin "P$13") (pinfunction "GND#4_P$13") (pintype "bidirectional"))
    )
    (net (code "132") (name "unconnected-(U$18-RSV-PadP$1)") (class "Default")
      (node (ref "U$18") (pin "P$1") (pinfunction "RSV_P$1") (pintype "bidirectional"))
    )
  )
)
